# analog_interfaces.net
KiCad netlist of a schematic drawn in Altium Designer
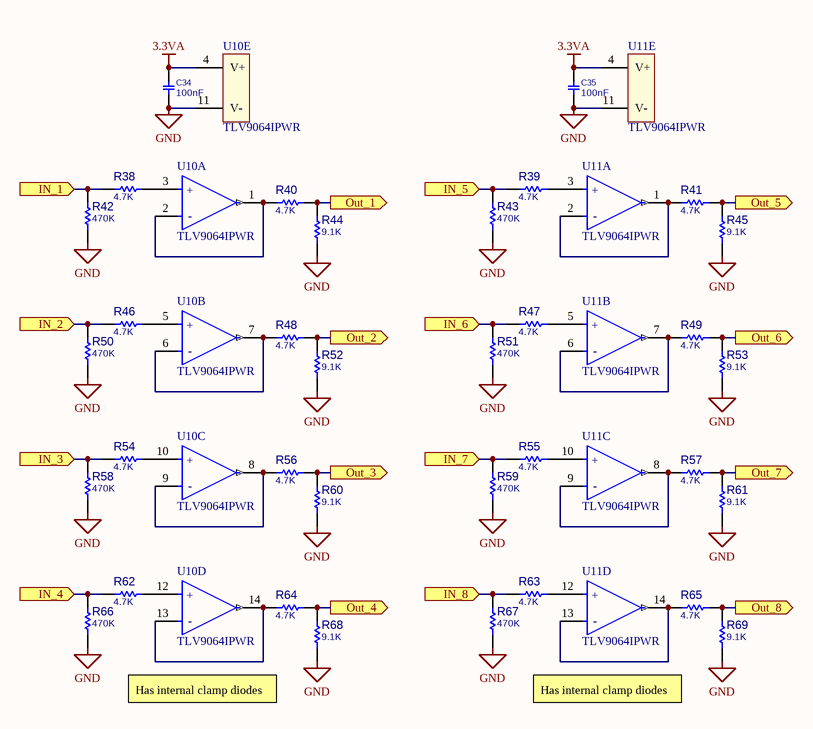
[diagram p0: analog_interfaces.SchDoc]

(export (version "E")
  (design (tool "Eeschema 10.0.6"))
  (components
    (comp (ref "C34")
      (value "100nF")
      (footprint "C0805")
      (description "CAP, MLCC")
      (fields (field (name "MANF_P#") "MANF_PART#") (field (name "MANF") "Murata"))
      (libsource (lib "passive_smd") (part "CAP_SMD_MLCC"))
    )
    (comp (ref "C35")
      (value "100nF")
      (footprint "C0805")
      (description "CAP, MLCC")
      (fields (field (name "MANF_P#") "MANF_PART#") (field (name "MANF") "Murata"))
      (libsource (lib "passive_smd") (part "CAP_SMD_MLCC"))
    )
    (comp (ref "R38")
      (value "4.7K")
      (footprint "R0805")
      (description "RESISTOR, SMD")
      (libsource (lib "passive_smd") (part "RES_SMD"))
    )
    (comp (ref "R39")
      (value "4.7K")
      (footprint "R0805")
      (description "RESISTOR, SMD")
      (libsource (lib "passive_smd") (part "RES_SMD"))
    )
    (comp (ref "R40")
      (value "4.7K")
      (footprint "R0805")
      (description "RESISTOR, SMD")
      (libsource (lib "passive_smd") (part "RES_SMD"))
    )
    (comp (ref "R41")
      (value "4.7K")
      (footprint "R0805")
      (description "RESISTOR, SMD")
      (libsource (lib "passive_smd") (part "RES_SMD"))
    )
    (comp (ref "R42")
      (value "470K")
      (footprint "R0805")
      (description "RESISTOR, SMD")
      (libsource (lib "passive_smd") (part "RES_SMD"))
    )
    (comp (ref "R43")
      (value "470K")
      (footprint "R0805")
      (description "RESISTOR, SMD")
      (libsource (lib "passive_smd") (part "RES_SMD"))
    )
    (comp (ref "R44")
      (value "9.1K")
      (footprint "R0805")
      (description "RESISTOR, SMD")
      (libsource (lib "passive_smd") (part "RES_SMD"))
    )
    (comp (ref "R45")
      (value "9.1K")
      (footprint "R0805")
      (description "RESISTOR, SMD")
      (libsource (lib "passive_smd") (part "RES_SMD"))
    )
    (comp (ref "R46")
      (value "4.7K")
      (footprint "R0805")
      (description "RESISTOR, SMD")
      (libsource (lib "passive_smd") (part "RES_SMD"))
    )
    (comp (ref "R47")
      (value "4.7K")
      (footprint "R0805")
      (description "RESISTOR, SMD")
      (libsource (lib "passive_smd") (part "RES_SMD"))
    )
    (comp (ref "R48")
      (value "4.7K")
      (footprint "R0805")
      (description "RESISTOR, SMD")
      (libsource (lib "passive_smd") (part "RES_SMD"))
    )
    (comp (ref "R49")
      (value "4.7K")
      (footprint "R0805")
      (description "RESISTOR, SMD")
      (libsource (lib "passive_smd") (part "RES_SMD"))
    )
    (comp (ref "R50")
      (value "470K")
      (footprint "R0805")
      (description "RESISTOR, SMD")
      (libsource (lib "passive_smd") (part "RES_SMD"))
    )
    (comp (ref "R51")
      (value "470K")
      (footprint "R0805")
      (description "RESISTOR, SMD")
      (libsource (lib "passive_smd") (part "RES_SMD"))
    )
    (comp (ref "R52")
      (value "9.1K")
      (footprint "R0805")
      (description "RESISTOR, SMD")
      (libsource (lib "passive_smd") (part "RES_SMD"))
    )
    (comp (ref "R53")
      (value "9.1K")
      (footprint "R0805")
      (description "RESISTOR, SMD")
      (libsource (lib "passive_smd") (part "RES_SMD"))
    )
    (comp (ref "R54")
      (value "4.7K")
      (footprint "R0805")
      (description "RESISTOR, SMD")
      (libsource (lib "passive_smd") (part "RES_SMD"))
    )
    (comp (ref "R55")
      (value "4.7K")
      (footprint "R0805")
      (description "RESISTOR, SMD")
      (libsource (lib "passive_smd") (part "RES_SMD"))
    )
    (comp (ref "R56")
      (value "4.7K")
      (footprint "R0805")
      (description "RESISTOR, SMD")
      (libsource (lib "passive_smd") (part "RES_SMD"))
    )
    (comp (ref "R57")
      (value "4.7K")
      (footprint "R0805")
      (description "RESISTOR, SMD")
      (libsource (lib "passive_smd") (part "RES_SMD"))
    )
    (comp (ref "R58")
      (value "470K")
      (footprint "R0805")
      (description "RESISTOR, SMD")
      (libsource (lib "passive_smd") (part "RES_SMD"))
    )
    (comp (ref "R59")
      (value "470K")
      (footprint "R0805")
      (description "RESISTOR, SMD")
      (libsource (lib "passive_smd") (part "RES_SMD"))
    )
    (comp (ref "R60")
      (value "9.1K")
      (footprint "R0805")
      (description "RESISTOR, SMD")
      (libsource (lib "passive_smd") (part "RES_SMD"))
    )
    (comp (ref "R61")
      (value "9.1K")
      (footprint "R0805")
      (description "RESISTOR, SMD")
      (libsource (lib "passive_smd") (part "RES_SMD"))
    )
    (comp (ref "R62")
      (value "4.7K")
      (footprint "R0805")
      (description "RESISTOR, SMD")
      (libsource (lib "passive_smd") (part "RES_SMD"))
    )
    (comp (ref "R63")
      (value "4.7K")
      (footprint "R0805")
      (description "RESISTOR, SMD")
      (libsource (lib "passive_smd") (part "RES_SMD"))
    )
    (comp (ref "R64")
      (value "4.7K")
      (footprint "R0805")
      (description "RESISTOR, SMD")
      (libsource (lib "passive_smd") (part "RES_SMD"))
    )
    (comp (ref "R65")
      (value "4.7K")
      (footprint "R0805")
      (description "RESISTOR, SMD")
      (libsource (lib "passive_smd") (part "RES_SMD"))
    )
    (comp (ref "R66")
      (value "470K")
      (footprint "R0805")
      (description "RESISTOR, SMD")
      (libsource (lib "passive_smd") (part "RES_SMD"))
    )
    (comp (ref "R67")
      (value "470K")
      (footprint "R0805")
      (description "RESISTOR, SMD")
      (libsource (lib "passive_smd") (part "RES_SMD"))
    )
    (comp (ref "R68")
      (value "9.1K")
      (footprint "R0805")
      (description "RESISTOR, SMD")
      (libsource (lib "passive_smd") (part "RES_SMD"))
    )
    (comp (ref "R69")
      (value "9.1K")
      (footprint "R0805")
      (description "RESISTOR, SMD")
      (libsource (lib "passive_smd") (part "RES_SMD"))
    )
    (comp (ref "U10")
      (value "TLV9064IPWR")
      (footprint "TTSOP-14")
      (description "IC CMOS 4 CIRCUIT 14TSSOP")
      (libsource (lib "Alib") (part "TLV9064"))
    )
    (comp (ref "U11")
      (value "TLV9064IPWR")
      (footprint "TTSOP-14")
      (description "IC CMOS 4 CIRCUIT 14TSSOP")
      (libsource (lib "Alib") (part "TLV9064"))
    )
  )
  (nets
    (net (code "1") (name "/IN_1") (class "Default")
      (node (ref "R38") (pin "2") (pinfunction "2_2") (pintype "passive"))
      (node (ref "R42") (pin "1") (pinfunction "1_1") (pintype "passive"))
    )
    (net (code "2") (name "/IN_2") (class "Default")
      (node (ref "R46") (pin "2") (pinfunction "2_2") (pintype "passive"))
      (node (ref "R50") (pin "1") (pinfunction "1_1") (pintype "passive"))
    )
    (net (code "3") (name "/IN_3") (class "Default")
      (node (ref "R54") (pin "2") (pinfunction "2_2") (pintype "passive"))
      (node (ref "R58") (pin "1") (pinfunction "1_1") (pintype "passive"))
    )
    (net (code "4") (name "/IN_4") (class "Default")
      (node (ref "R62") (pin "2") (pinfunction "2_2") (pintype "passive"))
      (node (ref "R66") (pin "1") (pinfunction "1_1") (pintype "passive"))
    )
    (net (code "5") (name "/IN_5") (class "Default")
      (node (ref "R39") (pin "2") (pinfunction "2_2") (pintype "passive"))
      (node (ref "R43") (pin "1") (pinfunction "1_1") (pintype "passive"))
    )
    (net (code "6") (name "/IN_6") (class "Default")
      (node (ref "R47") (pin "2") (pinfunction "2_2") (pintype "passive"))
      (node (ref "R51") (pin "1") (pinfunction "1_1") (pintype "passive"))
    )
    (net (code "7") (name "/IN_7") (class "Default")
      (node (ref "R55") (pin "2") (pinfunction "2_2") (pintype "passive"))
      (node (ref "R59") (pin "1") (pinfunction "1_1") (pintype "passive"))
    )
    (net (code "8") (name "/IN_8") (class "Default")
      (node (ref "R63") (pin "2") (pinfunction "2_2") (pintype "passive"))
      (node (ref "R67") (pin "1") (pinfunction "1_1") (pintype "passive"))
    )
    (net (code "9") (name "/Out_1") (class "Default")
      (node (ref "R40") (pin "1") (pinfunction "1_1") (pintype "passive"))
      (node (ref "R44") (pin "1") (pinfunction "1_1") (pintype "passive"))
    )
    (net (code "10") (name "/Out_2") (class "Default")
      (node (ref "R48") (pin "1") (pinfunction "1_1") (pintype "passive"))
      (node (ref "R52") (pin "1") (pinfunction "1_1") (pintype "passive"))
    )
    (net (code "11") (name "/Out_3") (class "Default")
      (node (ref "R56") (pin "1") (pinfunction "1_1") (pintype "passive"))
      (node (ref "R60") (pin "1") (pinfunction "1_1") (pintype "passive"))
    )
    (net (code "12") (name "/Out_4") (class "Default")
      (node (ref "R64") (pin "1") (pinfunction "1_1") (pintype "passive"))
      (node (ref "R68") (pin "1") (pinfunction "1_1") (pintype "passive"))
    )
    (net (code "13") (name "/Out_5") (class "Default")
      (node (ref "R41") (pin "1") (pinfunction "1_1") (pintype "passive"))
      (node (ref "R45") (pin "1") (pinfunction "1_1") (pintype "passive"))
    )
    (net (code "14") (name "/Out_6") (class "Default")
      (node (ref "R49") (pin "1") (pinfunction "1_1") (pintype "passive"))
      (node (ref "R53") (pin "1") (pinfunction "1_1") (pintype "passive"))
    )
    (net (code "15") (name "/Out_7") (class "Default")
      (node (ref "R57") (pin "1") (pinfunction "1_1") (pintype "passive"))
      (node (ref "R61") (pin "1") (pinfunction "1_1") (pintype "passive"))
    )
    (net (code "16") (name "/Out_8") (class "Default")
      (node (ref "R65") (pin "1") (pinfunction "1_1") (pintype "passive"))
      (node (ref "R69") (pin "1") (pinfunction "1_1") (pintype "passive"))
    )
    (net (code "17") (name "3.3VA") (class "Default")
      (node (ref "C34") (pin "2") (pinfunction "2_2") (pintype "passive"))
      (node (ref "C35") (pin "2") (pinfunction "2_2") (pintype "passive"))
      (node (ref "U10") (pin "4") (pinfunction "V+_4") (pintype "power_in"))
      (node (ref "U11") (pin "4") (pinfunction "V+_4") (pintype "power_in"))
    )
    (net (code "18") (name "GND") (class "Default")
      (node (ref "C34") (pin "1") (pinfunction "1_1") (pintype "passive"))
      (node (ref "C35") (pin "1") (pinfunction "1_1") (pintype "passive"))
      (node (ref "R42") (pin "2") (pinfunction "2_2") (pintype "passive"))
      (node (ref "R43") (pin "2") (pinfunction "2_2") (pintype "passive"))
      (node (ref "R44") (pin "2") (pinfunction "2_2") (pintype "passive"))
      (node (ref "R45") (pin "2") (pinfunction "2_2") (pintype "passive"))
      (node (ref "R50") (pin "2") (pinfunction "2_2") (pintype "passive"))
      (node (ref "R51") (pin "2") (pinfunction "2_2") (pintype "passive"))
      (node (ref "R52") (pin "2") (pinfunction "2_2") (pintype "passive"))
      (node (ref "R53") (pin "2") (pinfunction "2_2") (pintype "passive"))
      (node (ref "R58") (pin "2") (pinfunction "2_2") (pintype "passive"))
      (node (ref "R59") (pin "2") (pinfunction "2_2") (pintype "passive"))
      (node (ref "R60") (pin "2") (pinfunction "2_2") (pintype "passive"))
      (node (ref "R61") (pin "2") (pinfunction "2_2") (pintype "passive"))
      (node (ref "R66") (pin "2") (pinfunction "2_2") (pintype "passive"))
      (node (ref "R67") (pin "2") (pinfunction "2_2") (pintype "passive"))
      (node (ref "R68") (pin "2") (pinfunction "2_2") (pintype "passive"))
      (node (ref "R69") (pin "2") (pinfunction "2_2") (pintype "passive"))
      (node (ref "U10") (pin "11") (pinfunction "V-_11") (pintype "power_in"))
      (node (ref "U11") (pin "11") (pinfunction "V-_11") (pintype "power_in"))
    )
    (net (code "19") (name "Net-(U10A-IN1+)") (class "Default")
      (node (ref "R38") (pin "1") (pinfunction "1_1") (pintype "passive"))
      (node (ref "U10") (pin "3") (pinfunction "IN1+_3") (pintype "tri_state"))
    )
    (net (code "20") (name "Net-(U10A-IN1-)") (class "Default")
      (node (ref "R40") (pin "2") (pinfunction "2_2") (pintype "passive"))
      (node (ref "U10") (pin "1") (pinfunction "OUT1_1") (pintype "output"))
      (node (ref "U10") (pin "2") (pinfunction "IN1-_2") (pintype "tri_state"))
    )
    (net (code "21") (name "Net-(U10B-IN2+)") (class "Default")
      (node (ref "R46") (pin "1") (pinfunction "1_1") (pintype "passive"))
      (node (ref "U10") (pin "5") (pinfunction "IN2+_5") (pintype "tri_state"))
    )
    (net (code "22") (name "Net-(U10B-IN2-)") (class "Default")
      (node (ref "R48") (pin "2") (pinfunction "2_2") (pintype "passive"))
      (node (ref "U10") (pin "6") (pinfunction "IN2-_6") (pintype "tri_state"))
      (node (ref "U10") (pin "7") (pinfunction "OUT2_7") (pintype "output"))
    )
    (net (code "23") (name "Net-(U10C-IN3+)") (class "Default")
      (node (ref "R54") (pin "1") (pinfunction "1_1") (pintype "passive"))
      (node (ref "U10") (pin "10") (pinfunction "IN3+_10") (pintype "tri_state"))
    )
    (net (code "24") (name "Net-(U10C-IN3-)") (class "Default")
      (node (ref "R56") (pin "2") (pinfunction "2_2") (pintype "passive"))
      (node (ref "U10") (pin "8") (pinfunction "OUT3_8") (pintype "output"))
      (node (ref "U10") (pin "9") (pinfunction "IN3-_9") (pintype "tri_state"))
    )
    (net (code "25") (name "Net-(U10D-IN4+)") (class "Default")
      (node (ref "R62") (pin "1") (pinfunction "1_1") (pintype "passive"))
      (node (ref "U10") (pin "12") (pinfunction "IN4+_12") (pintype "tri_state"))
    )
    (net (code "26") (name "Net-(U10D-IN4-)") (class "Default")
      (node (ref "R64") (pin "2") (pinfunction "2_2") (pintype "passive"))
      (node (ref "U10") (pin "13") (pinfunction "IN4-_13") (pintype "tri_state"))
      (node (ref "U10") (pin "14") (pinfunction "OUT4_14") (pintype "output"))
    )
    (net (code "27") (name "Net-(U11A-IN1+)") (class "Default")
      (node (ref "R39") (pin "1") (pinfunction "1_1") (pintype "passive"))
      (node (ref "U11") (pin "3") (pinfunction "IN1+_3") (pintype "tri_state"))
    )
    (net (code "28") (name "Net-(U11A-IN1-)") (class "Default")
      (node (ref "R41") (pin "2") (pinfunction "2_2") (pintype "passive"))
      (node (ref "U11") (pin "1") (pinfunction "OUT1_1") (pintype "output"))
      (node (ref "U11") (pin "2") (pinfunction "IN1-_2") (pintype "tri_state"))
    )
    (net (code "29") (name "Net-(U11B-IN2+)") (class "Default")
      (node (ref "R47") (pin "1") (pinfunction "1_1") (pintype "passive"))
      (node (ref "U11") (pin "5") (pinfunction "IN2+_5") (pintype "tri_state"))
    )
    (net (code "30") (name "Net-(U11B-IN2-)") (class "Default")
      (node (ref "R49") (pin "2") (pinfunction "2_2") (pintype "passive"))
      (node (ref "U11") (pin "6") (pinfunction "IN2-_6") (pintype "tri_state"))
      (node (ref "U11") (pin "7") (pinfunction "OUT2_7") (pintype "output"))
    )
    (net (code "31") (name "Net-(U11C-IN3+)") (class "Default")
      (node (ref "R55") (pin "1") (pinfunction "1_1") (pintype "passive"))
      (node (ref "U11") (pin "10") (pinfunction "IN3+_10") (pintype "tri_state"))
    )
    (net (code "32") (name "Net-(U11C-IN3-)") (class "Default")
      (node (ref "R57") (pin "2") (pinfunction "2_2") (pintype "passive"))
      (node (ref "U11") (pin "8") (pinfunction "OUT3_8") (pintype "output"))
      (node (ref "U11") (pin "9") (pinfunction "IN3-_9") (pintype "tri_state"))
    )
    (net (code "33") (name "Net-(U11D-IN4+)") (class "Default")
      (node (ref "R63") (pin "1") (pinfunction "1_1") (pintype "passive"))
      (node (ref "U11") (pin "12") (pinfunction "IN4+_12") (pintype "tri_state"))
    )
    (net (code "34") (name "Net-(U11D-IN4-)") (class "Default")
      (node (ref "R65") (pin "2") (pinfunction "2_2") (pintype "passive"))
      (node (ref "U11") (pin "13") (pinfunction "IN4-_13") (pintype "tri_state"))
      (node (ref "U11") (pin "14") (pinfunction "OUT4_14") (pintype "output"))
    )
  )
)
